# SH6_-_HIGH_SIDE_DRIVER.net
KiCad netlist of a schematic drawn in Altium Designer
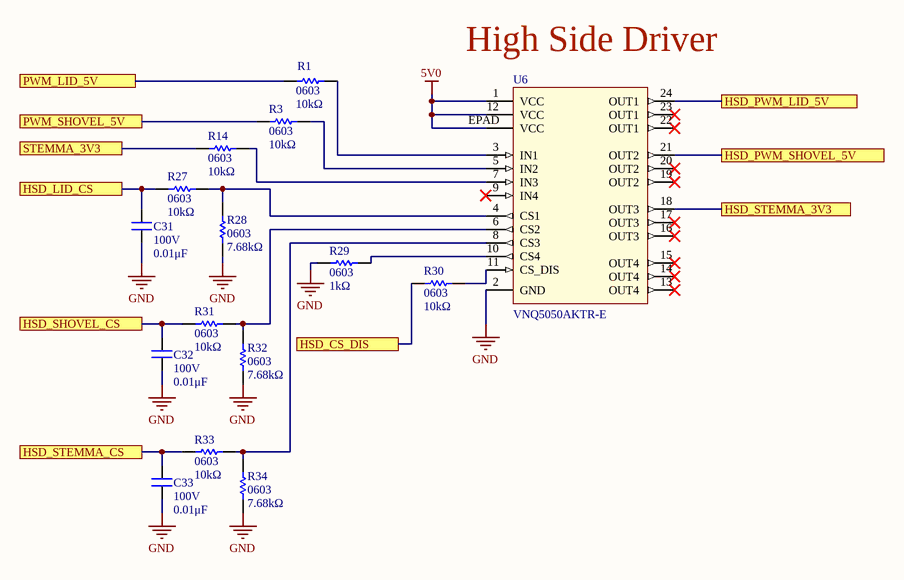
[diagram p0: SH6 - HIGH SIDE DRIVER.SchDoc]

(export (version "E")
  (design (tool "Eeschema 10.0.6"))
  (components
    (comp (ref "C31")
      (value "0.01μF")
      (footprint "CAP0603")
      (description "CAP CER 10000PF 100V X7R 0603")
      (fields (field (name "VOLTAGE RATING") "100V") (field (name "Comment") "CAP_0.01uF_100V_0603"))
      (libsource (lib "UWRT_Schematic_Library_2020") (part "CAP_0.01uF_100V_0603"))
    )
    (comp (ref "C32")
      (value "0.01μF")
      (footprint "CAP0603")
      (description "CAP CER 10000PF 100V X7R 0603")
      (fields (field (name "VOLTAGE RATING") "100V") (field (name "Comment") "CAP_0.01uF_100V_0603"))
      (libsource (lib "UWRT_Schematic_Library_2020") (part "CAP_0.01uF_100V_0603"))
    )
    (comp (ref "C33")
      (value "0.01μF")
      (footprint "CAP0603")
      (description "CAP CER 10000PF 100V X7R 0603")
      (fields (field (name "VOLTAGE RATING") "100V") (field (name "Comment") "CAP_0.01uF_100V_0603"))
      (libsource (lib "UWRT_Schematic_Library_2020") (part "CAP_0.01uF_100V_0603"))
    )
    (comp (ref "R1")
      (value "10kΩ")
      (footprint "RESC0603")
      (description "RES 10K OHM 5% 1/10W 0603")
      (fields (field (name "PACKAGE/FOOTPRINT") "0603") (field (name "Comment") "RES_10kΩ_0603_5%"))
      (libsource (lib "UWRT_Schematic_Library_2020") (part "RES_10kΩ_0603_5%"))
    )
    (comp (ref "R3")
      (value "10kΩ")
      (footprint "RESC0603")
      (description "RES 10K OHM 5% 1/10W 0603")
      (fields (field (name "PACKAGE/FOOTPRINT") "0603") (field (name "Comment") "RES_10kΩ_0603_5%"))
      (libsource (lib "UWRT_Schematic_Library_2020") (part "RES_10kΩ_0603_5%"))
    )
    (comp (ref "R14")
      (value "10kΩ")
      (footprint "RESC0603")
      (description "RES 10K OHM 5% 1/10W 0603")
      (fields (field (name "PACKAGE/FOOTPRINT") "0603") (field (name "Comment") "RES_10kΩ_0603_5%"))
      (libsource (lib "UWRT_Schematic_Library_2020") (part "RES_10kΩ_0603_5%"))
    )
    (comp (ref "R27")
      (value "10kΩ")
      (footprint "RESC0603")
      (description "RES 10K OHM 5% 1/10W 0603")
      (fields (field (name "PACKAGE/FOOTPRINT") "0603") (field (name "Comment") "RES_10kΩ_0603_5%"))
      (libsource (lib "UWRT_Schematic_Library_2020") (part "RES_10kΩ_0603_5%"))
    )
    (comp (ref "R28")
      (value "7.68kΩ")
      (footprint "RESC0603")
      (description "RES SMD 7.68K OHM 1% 1/10W 0603")
      (fields
        (field (name "TOLERANCE") "1%")
        (field (name "PACKAGE") "0603")
        (field (name "Comment") "RES_7.68kΩ_0603")
      )
      (libsource (lib "UWRT_Schematic_Library_2020") (part "RES_7.68kΩ_0603_1%"))
    )
    (comp (ref "R29")
      (value "1kΩ")
      (footprint "RESC0603")
      (description "RES 1K OHM 5% 1/10W 0603")
      (fields (field (name "PACKAGE/FOOTPRINT") "0603") (field (name "Comment") "RES_1kΩ_0603_5%"))
      (libsource (lib "UWRT_Schematic_Library_2020") (part "RES_1kΩ_0603_5%"))
    )
    (comp (ref "R30")
      (value "10kΩ")
      (footprint "RESC0603")
      (description "RES 10K OHM 5% 1/10W 0603")
      (fields (field (name "PACKAGE/FOOTPRINT") "0603") (field (name "Comment") "RES_10kΩ_0603_5%"))
      (libsource (lib "UWRT_Schematic_Library_2020") (part "RES_10kΩ_0603_5%"))
    )
    (comp (ref "R31")
      (value "10kΩ")
      (footprint "RESC0603")
      (description "RES 10K OHM 5% 1/10W 0603")
      (fields (field (name "PACKAGE/FOOTPRINT") "0603") (field (name "Comment") "RES_10kΩ_0603_5%"))
      (libsource (lib "UWRT_Schematic_Library_2020") (part "RES_10kΩ_0603_5%"))
    )
    (comp (ref "R32")
      (value "7.68kΩ")
      (footprint "RESC0603")
      (description "RES SMD 7.68K OHM 1% 1/10W 0603")
      (fields
        (field (name "TOLERANCE") "1%")
        (field (name "PACKAGE") "0603")
        (field (name "Comment") "RES_7.68kΩ_0603")
      )
      (libsource (lib "UWRT_Schematic_Library_2020") (part "RES_7.68kΩ_0603_1%"))
    )
    (comp (ref "R33")
      (value "10kΩ")
      (footprint "RESC0603")
      (description "RES 10K OHM 5% 1/10W 0603")
      (fields (field (name "PACKAGE/FOOTPRINT") "0603") (field (name "Comment") "RES_10kΩ_0603_5%"))
      (libsource (lib "UWRT_Schematic_Library_2020") (part "RES_10kΩ_0603_5%"))
    )
    (comp (ref "R34")
      (value "7.68kΩ")
      (footprint "RESC0603")
      (description "RES SMD 7.68K OHM 1% 1/10W 0603")
      (fields
        (field (name "TOLERANCE") "1%")
        (field (name "PACKAGE") "0603")
        (field (name "Comment") "RES_7.68kΩ_0603")
      )
      (libsource (lib "UWRT_Schematic_Library_2020") (part "RES_7.68kΩ_0603_1%"))
    )
    (comp (ref "U6")
      (value "VNQ5050AKTR-E")
      (footprint "PowerSSO-24_STM")
      (description "High Side Driver 24-Pin PowerSSO EP T/R")
      (fields (field (name "MANUFACTURER PART NUMBER 1") "VNQ5050AKTR-E"))
      (libsource (lib "UWRT_Schematic_Library_2020") (part "VNQ5050AKTR-E"))
    )
  )
  (nets
    (net (code "1") (name "/HSD_CS_DIS") (class "Default")
      (node (ref "R30") (pin "1") (pinfunction "1_1") (pintype "passive"))
    )
    (net (code "2") (name "/HSD_LID_CS") (class "Default")
      (node (ref "C31") (pin "2") (pinfunction "2_2") (pintype "passive"))
      (node (ref "R27") (pin "1") (pinfunction "1_1") (pintype "passive"))
    )
    (net (code "3") (name "/HSD_PWM_LID_5V") (class "Default")
      (node (ref "U6") (pin "24") (pinfunction "OUT1_24") (pintype "output"))
    )
    (net (code "4") (name "/HSD_PWM_SHOVEL_5V") (class "Default")
      (node (ref "U6") (pin "21") (pinfunction "OUT2_21") (pintype "output"))
    )
    (net (code "5") (name "/HSD_SHOVEL_CS") (class "Default")
      (node (ref "C32") (pin "2") (pinfunction "2_2") (pintype "passive"))
      (node (ref "R31") (pin "1") (pinfunction "1_1") (pintype "passive"))
    )
    (net (code "6") (name "/HSD_STEMMA_3V3") (class "Default")
      (node (ref "U6") (pin "18") (pinfunction "OUT3_18") (pintype "output"))
    )
    (net (code "7") (name "/HSD_STEMMA_CS") (class "Default")
      (node (ref "C33") (pin "2") (pinfunction "2_2") (pintype "passive"))
      (node (ref "R33") (pin "1") (pinfunction "1_1") (pintype "passive"))
    )
    (net (code "8") (name "/PWM_LID_5V") (class "Default")
      (node (ref "R1") (pin "1") (pinfunction "1_1") (pintype "passive"))
    )
    (net (code "9") (name "/PWM_SHOVEL_5V") (class "Default")
      (node (ref "R3") (pin "1") (pinfunction "1_1") (pintype "passive"))
    )
    (net (code "10") (name "/STEMMA_3V3") (class "Default")
      (node (ref "R14") (pin "1") (pinfunction "1_1") (pintype "passive"))
    )
    (net (code "11") (name "5V0") (class "Default")
      (node (ref "U6") (pin "1") (pinfunction "VCC_1") (pintype "power_in"))
      (node (ref "U6") (pin "12") (pinfunction "VCC_12") (pintype "power_in"))
      (node (ref "U6") (pin "EPAD") (pinfunction "VCC_EPAD") (pintype "power_in"))
    )
    (net (code "12") (name "GND") (class "Default")
      (node (ref "C31") (pin "1") (pinfunction "1_1") (pintype "passive"))
      (node (ref "C32") (pin "1") (pinfunction "1_1") (pintype "passive"))
      (node (ref "C33") (pin "1") (pinfunction "1_1") (pintype "passive"))
      (node (ref "R28") (pin "1") (pinfunction "1_1") (pintype "passive"))
      (node (ref "R29") (pin "1") (pinfunction "1_1") (pintype "passive"))
      (node (ref "R32") (pin "1") (pinfunction "1_1") (pintype "passive"))
      (node (ref "R34") (pin "1") (pinfunction "1_1") (pintype "passive"))
      (node (ref "U6") (pin "2") (pinfunction "GND_2") (pintype "power_in"))
    )
    (net (code "13") (name "Net-(U6-CS1)") (class "Default")
      (node (ref "R27") (pin "2") (pinfunction "2_2") (pintype "passive"))
      (node (ref "R28") (pin "2") (pinfunction "2_2") (pintype "passive"))
      (node (ref "U6") (pin "4") (pinfunction "CS1_4") (pintype "output"))
    )
    (net (code "14") (name "Net-(U6-CS2)") (class "Default")
      (node (ref "R31") (pin "2") (pinfunction "2_2") (pintype "passive"))
      (node (ref "R32") (pin "2") (pinfunction "2_2") (pintype "passive"))
      (node (ref "U6") (pin "6") (pinfunction "CS2_6") (pintype "output"))
    )
    (net (code "15") (name "Net-(U6-CS3)") (class "Default")
      (node (ref "R33") (pin "2") (pinfunction "2_2") (pintype "passive"))
      (node (ref "R34") (pin "2") (pinfunction "2_2") (pintype "passive"))
      (node (ref "U6") (pin "8") (pinfunction "CS3_8") (pintype "output"))
    )
    (net (code "16") (name "Net-(U6-CS4)") (class "Default")
      (node (ref "R29") (pin "2") (pinfunction "2_2") (pintype "passive"))
      (node (ref "U6") (pin "10") (pinfunction "CS4_10") (pintype "output"))
    )
    (net (code "17") (name "Net-(U6-CS_DIS)") (class "Default")
      (node (ref "R30") (pin "2") (pinfunction "2_2") (pintype "passive"))
      (node (ref "U6") (pin "11") (pinfunction "CS_DIS_11") (pintype "input"))
    )
    (net (code "18") (name "Net-(U6-IN1)") (class "Default")
      (node (ref "R1") (pin "2") (pinfunction "2_2") (pintype "passive"))
      (node (ref "U6") (pin "3") (pinfunction "IN1_3") (pintype "input"))
    )
    (net (code "19") (name "Net-(U6-IN2)") (class "Default")
      (node (ref "R3") (pin "2") (pinfunction "2_2") (pintype "passive"))
      (node (ref "U6") (pin "5") (pinfunction "IN2_5") (pintype "input"))
    )
    (net (code "20") (name "Net-(U6-IN3)") (class "Default")
      (node (ref "R14") (pin "2") (pinfunction "2_2") (pintype "passive"))
      (node (ref "U6") (pin "7") (pinfunction "IN3_7") (pintype "input"))
    )
    (net (code "21") (name "unconnected-(U6-IN4-Pad9)") (class "Default")
      (node (ref "U6") (pin "9") (pinfunction "IN4_9") (pintype "input+no_connect"))
    )
    (net (code "22") (name "unconnected-(U6-OUT1-Pad22)") (class "Default")
      (node (ref "U6") (pin "22") (pinfunction "OUT1_22") (pintype "output+no_connect"))
    )
    (net (code "23") (name "unconnected-(U6-OUT1-Pad23)") (class "Default")
      (node (ref "U6") (pin "23") (pinfunction "OUT1_23") (pintype "output+no_connect"))
    )
    (net (code "24") (name "unconnected-(U6-OUT2-Pad19)") (class "Default")
      (node (ref "U6") (pin "19") (pinfunction "OUT2_19") (pintype "output+no_connect"))
    )
    (net (code "25") (name "unconnected-(U6-OUT2-Pad20)") (class "Default")
      (node (ref "U6") (pin "20") (pinfunction "OUT2_20") (pintype "output+no_connect"))
    )
    (net (code "26") (name "unconnected-(U6-OUT3-Pad16)") (class "Default")
      (node (ref "U6") (pin "16") (pinfunction "OUT3_16") (pintype "output+no_connect"))
    )
    (net (code "27") (name "unconnected-(U6-OUT3-Pad17)") (class "Default")
      (node (ref "U6") (pin "17") (pinfunction "OUT3_17") (pintype "output+no_connect"))
    )
    (net (code "28") (name "unconnected-(U6-OUT4-Pad13)") (class "Default")
      (node (ref "U6") (pin "13") (pinfunction "OUT4_13") (pintype "output+no_connect"))
    )
    (net (code "29") (name "unconnected-(U6-OUT4-Pad14)") (class "Default")
      (node (ref "U6") (pin "14") (pinfunction "OUT4_14") (pintype "output+no_connect"))
    )
    (net (code "30") (name "unconnected-(U6-OUT4-Pad15)") (class "Default")
      (node (ref "U6") (pin "15") (pinfunction "OUT4_15") (pintype "output+no_connect"))
    )
  )
)
